# shield_template.net
KiCad netlist of a schematic drawn in EAGLE
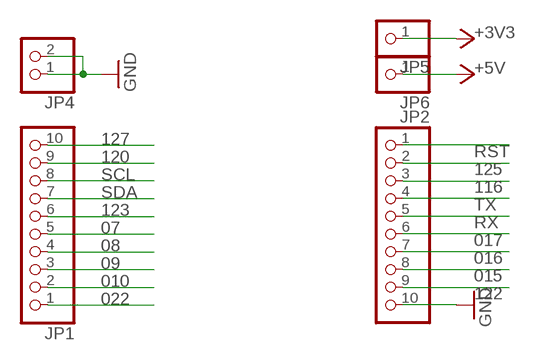
[diagram p0: schematic, sheet 1]

(export (version "E")
  (design (tool "Eeschema 10.0.6"))
  (components
    (comp (ref "JP1")
      (value "PINHD-1X10_2.54")
      (footprint "eagle-import:1X10")
      (libsource (lib "eagle-import") (part "PINHD-1X10_2.54"))
    )
    (comp (ref "JP2")
      (value "PINHD-1X10_2.54")
      (footprint "eagle-import:1X10")
      (libsource (lib "eagle-import") (part "PINHD-1X10_2.54"))
    )
    (comp (ref "JP4")
      (value "PINHD-1X02_2.54")
      (footprint "eagle-import:1X02")
      (libsource (lib "eagle-import") (part "PINHD-1X02_2.54"))
    )
    (comp (ref "JP5")
      (value "PINHD-1X1")
      (footprint "eagle-import:1X01")
      (libsource (lib "eagle-import") (part "PINHD-1X1"))
    )
    (comp (ref "JP6")
      (value "PINHD-1X1")
      (footprint "eagle-import:1X01")
      (libsource (lib "eagle-import") (part "PINHD-1X1"))
    )
  )
  (nets
    (net (code "1") (name "+3V3") (class "Default")
      (node (ref "JP5") (pin "1") (pinfunction "1_1") (pintype "passive"))
    )
    (net (code "2") (name "+5V") (class "Default")
      (node (ref "JP6") (pin "1") (pinfunction "1_1") (pintype "passive"))
    )
    (net (code "3") (name "/07") (class "Default")
      (node (ref "JP1") (pin "5") (pinfunction "5_5") (pintype "passive"))
    )
    (net (code "4") (name "/08") (class "Default")
      (node (ref "JP1") (pin "4") (pinfunction "4_4") (pintype "passive"))
    )
    (net (code "5") (name "/09") (class "Default")
      (node (ref "JP1") (pin "3") (pinfunction "3_3") (pintype "passive"))
    )
    (net (code "6") (name "/010") (class "Default")
      (node (ref "JP1") (pin "2") (pinfunction "2_2") (pintype "passive"))
    )
    (net (code "7") (name "/015") (class "Default")
      (node (ref "JP2") (pin "8") (pinfunction "8_8") (pintype "passive"))
    )
    (net (code "8") (name "/016") (class "Default")
      (node (ref "JP2") (pin "7") (pinfunction "7_7") (pintype "passive"))
    )
    (net (code "9") (name "/017") (class "Default")
      (node (ref "JP2") (pin "6") (pinfunction "6_6") (pintype "passive"))
    )
    (net (code "10") (name "/022") (class "Default")
      (node (ref "JP1") (pin "1") (pinfunction "1_1") (pintype "passive"))
    )
    (net (code "11") (name "/116") (class "Default")
      (node (ref "JP2") (pin "3") (pinfunction "3_3") (pintype "passive"))
    )
    (net (code "12") (name "/120") (class "Default")
      (node (ref "JP1") (pin "9") (pinfunction "9_9") (pintype "passive"))
    )
    (net (code "13") (name "/122") (class "Default")
      (node (ref "JP2") (pin "9") (pinfunction "9_9") (pintype "passive"))
    )
    (net (code "14") (name "/123") (class "Default")
      (node (ref "JP1") (pin "6") (pinfunction "6_6") (pintype "passive"))
    )
    (net (code "15") (name "/125") (class "Default")
      (node (ref "JP2") (pin "2") (pinfunction "2_2") (pintype "passive"))
    )
    (net (code "16") (name "/127") (class "Default")
      (node (ref "JP1") (pin "10") (pinfunction "10_10") (pintype "passive"))
    )
    (net (code "17") (name "/RST") (class "Default")
      (node (ref "JP2") (pin "1") (pinfunction "1_1") (pintype "passive"))
    )
    (net (code "18") (name "/RX") (class "Default")
      (node (ref "JP2") (pin "5") (pinfunction "5_5") (pintype "passive"))
    )
    (net (code "19") (name "/SCL") (class "Default")
      (node (ref "JP1") (pin "8") (pinfunction "8_8") (pintype "passive"))
    )
    (net (code "20") (name "/SDA") (class "Default")
      (node (ref "JP1") (pin "7") (pinfunction "7_7") (pintype "passive"))
    )
    (net (code "21") (name "/TX") (class "Default")
      (node (ref "JP2") (pin "4") (pinfunction "4_4") (pintype "passive"))
    )
    (net (code "22") (name "GND") (class "Default")
      (node (ref "JP2") (pin "10") (pinfunction "10_10") (pintype "passive"))
      (node (ref "JP4") (pin "1") (pinfunction "1_1") (pintype "passive"))
      (node (ref "JP4") (pin "2") (pinfunction "2_2") (pintype "passive"))
    )
  )
)
